# hv_filter.net
KiCad netlist of a schematic drawn in EAGLE
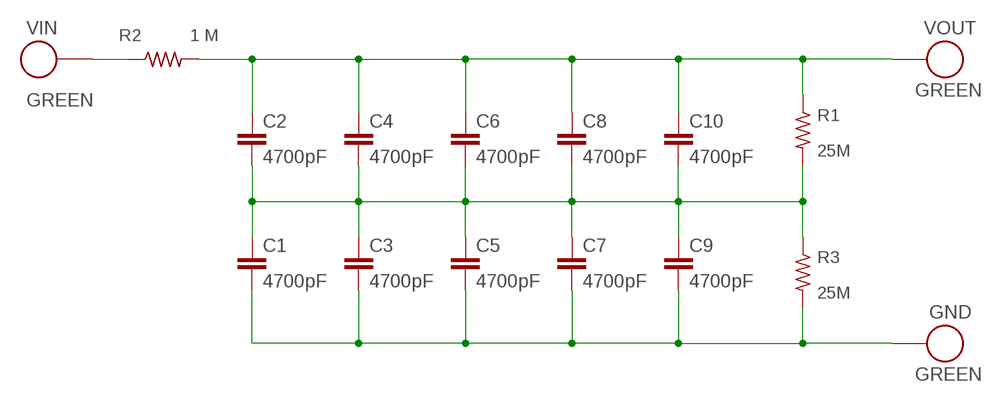
[diagram p0: schematic, sheet 1]

(export (version "E")
  (design (tool "Eeschema 10.0.6"))
  (components
    (comp (ref "C1")
      (value "4700pF")
      (footprint "eagle-import:4700PF6KV")
      (libsource (lib "eagle-import") (part "4700PF6KV"))
    )
    (comp (ref "C2")
      (value "4700pF")
      (footprint "eagle-import:4700PF6KV")
      (libsource (lib "eagle-import") (part "4700PF6KV"))
    )
    (comp (ref "C3")
      (value "4700pF")
      (footprint "eagle-import:4700PF6KV")
      (libsource (lib "eagle-import") (part "4700PF6KV"))
    )
    (comp (ref "C4")
      (value "4700pF")
      (footprint "eagle-import:4700PF6KV")
      (libsource (lib "eagle-import") (part "4700PF6KV"))
    )
    (comp (ref "C5")
      (value "4700pF")
      (footprint "eagle-import:4700PF6KV")
      (libsource (lib "eagle-import") (part "4700PF6KV"))
    )
    (comp (ref "C6")
      (value "4700pF")
      (footprint "eagle-import:4700PF6KV")
      (libsource (lib "eagle-import") (part "4700PF6KV"))
    )
    (comp (ref "C7")
      (value "4700pF")
      (footprint "eagle-import:4700PF6KV")
      (libsource (lib "eagle-import") (part "4700PF6KV"))
    )
    (comp (ref "C8")
      (value "4700pF")
      (footprint "eagle-import:4700PF6KV")
      (libsource (lib "eagle-import") (part "4700PF6KV"))
    )
    (comp (ref "C9")
      (value "4700pF")
      (footprint "eagle-import:4700PF6KV")
      (libsource (lib "eagle-import") (part "4700PF6KV"))
    )
    (comp (ref "C10")
      (value "4700pF")
      (footprint "eagle-import:4700PF6KV")
      (libsource (lib "eagle-import") (part "4700PF6KV"))
    )
    (comp (ref "GND")
      (value "GREEN")
      (footprint "eagle-import:AWG22")
      (fields (field (name "MPN") "108-0904-001"))
      (libsource (lib "eagle-import") (part "BANANA_JACK_GREEN"))
    )
    (comp (ref "R1")
      (value "25M")
      (footprint "eagle-import:25MOHM")
      (libsource (lib "eagle-import") (part "25MOHM"))
    )
    (comp (ref "R2")
      (value "1 M")
      (footprint "eagle-import:1M20KV")
      (libsource (lib "eagle-import") (part "1M25KV"))
    )
    (comp (ref "R3")
      (value "25M")
      (footprint "eagle-import:25MOHM")
      (libsource (lib "eagle-import") (part "25MOHM"))
    )
    (comp (ref "VIN")
      (value "GREEN")
      (footprint "eagle-import:AWG22")
      (fields (field (name "MPN") "108-0904-001"))
      (libsource (lib "eagle-import") (part "BANANA_JACK_GREEN"))
    )
    (comp (ref "VOUT")
      (value "GREEN")
      (footprint "eagle-import:AWG22")
      (fields (field (name "MPN") "108-0904-001"))
      (libsource (lib "eagle-import") (part "BANANA_JACK_GREEN"))
    )
  )
  (nets
    (net (code "1") (name "Net-(C1-1)") (class "Default")
      (node (ref "C1") (pin "P$1") (pinfunction "1_P$1") (pintype "passive"))
      (node (ref "C10") (pin "P$2") (pinfunction "2_P$2") (pintype "passive"))
      (node (ref "C2") (pin "P$2") (pinfunction "2_P$2") (pintype "passive"))
      (node (ref "C3") (pin "P$1") (pinfunction "1_P$1") (pintype "passive"))
      (node (ref "C4") (pin "P$2") (pinfunction "2_P$2") (pintype "passive"))
      (node (ref "C5") (pin "P$1") (pinfunction "1_P$1") (pintype "passive"))
      (node (ref "C6") (pin "P$2") (pinfunction "2_P$2") (pintype "passive"))
      (node (ref "C7") (pin "P$1") (pinfunction "1_P$1") (pintype "passive"))
      (node (ref "C8") (pin "P$2") (pinfunction "2_P$2") (pintype "passive"))
      (node (ref "C9") (pin "P$1") (pinfunction "1_P$1") (pintype "passive"))
      (node (ref "R1") (pin "P$2") (pinfunction "P$2_P$2") (pintype "passive"))
      (node (ref "R3") (pin "P$1") (pinfunction "P$1_P$1") (pintype "passive"))
    )
    (net (code "2") (name "Net-(C1-2)") (class "Default")
      (node (ref "C1") (pin "P$2") (pinfunction "2_P$2") (pintype "passive"))
      (node (ref "C3") (pin "P$2") (pinfunction "2_P$2") (pintype "passive"))
      (node (ref "C5") (pin "P$2") (pinfunction "2_P$2") (pintype "passive"))
      (node (ref "C7") (pin "P$2") (pinfunction "2_P$2") (pintype "passive"))
      (node (ref "C9") (pin "P$2") (pinfunction "2_P$2") (pintype "passive"))
      (node (ref "GND") (pin "P$1") (pinfunction "P$1_P$1") (pintype "bidirectional"))
      (node (ref "R3") (pin "P$2") (pinfunction "P$2_P$2") (pintype "passive"))
    )
    (net (code "3") (name "Net-(C10-1)") (class "Default")
      (node (ref "C10") (pin "P$1") (pinfunction "1_P$1") (pintype "passive"))
      (node (ref "C2") (pin "P$1") (pinfunction "1_P$1") (pintype "passive"))
      (node (ref "C4") (pin "P$1") (pinfunction "1_P$1") (pintype "passive"))
      (node (ref "C6") (pin "P$1") (pinfunction "1_P$1") (pintype "passive"))
      (node (ref "C8") (pin "P$1") (pinfunction "1_P$1") (pintype "passive"))
      (node (ref "R1") (pin "P$1") (pinfunction "P$1_P$1") (pintype "passive"))
      (node (ref "R2") (pin "P$2") (pinfunction "P$2_P$2") (pintype "passive"))
      (node (ref "VOUT") (pin "P$1") (pinfunction "P$1_P$1") (pintype "bidirectional"))
    )
    (net (code "4") (name "Net-(R2-PadP$1)") (class "Default")
      (node (ref "R2") (pin "P$1") (pinfunction "P$1_P$1") (pintype "passive"))
      (node (ref "VIN") (pin "P$1") (pinfunction "P$1_P$1") (pintype "bidirectional"))
    )
  )
)
